# A3010_Adelaide_Keyboard.net
KiCad netlist of a schematic drawn in Altium Designer
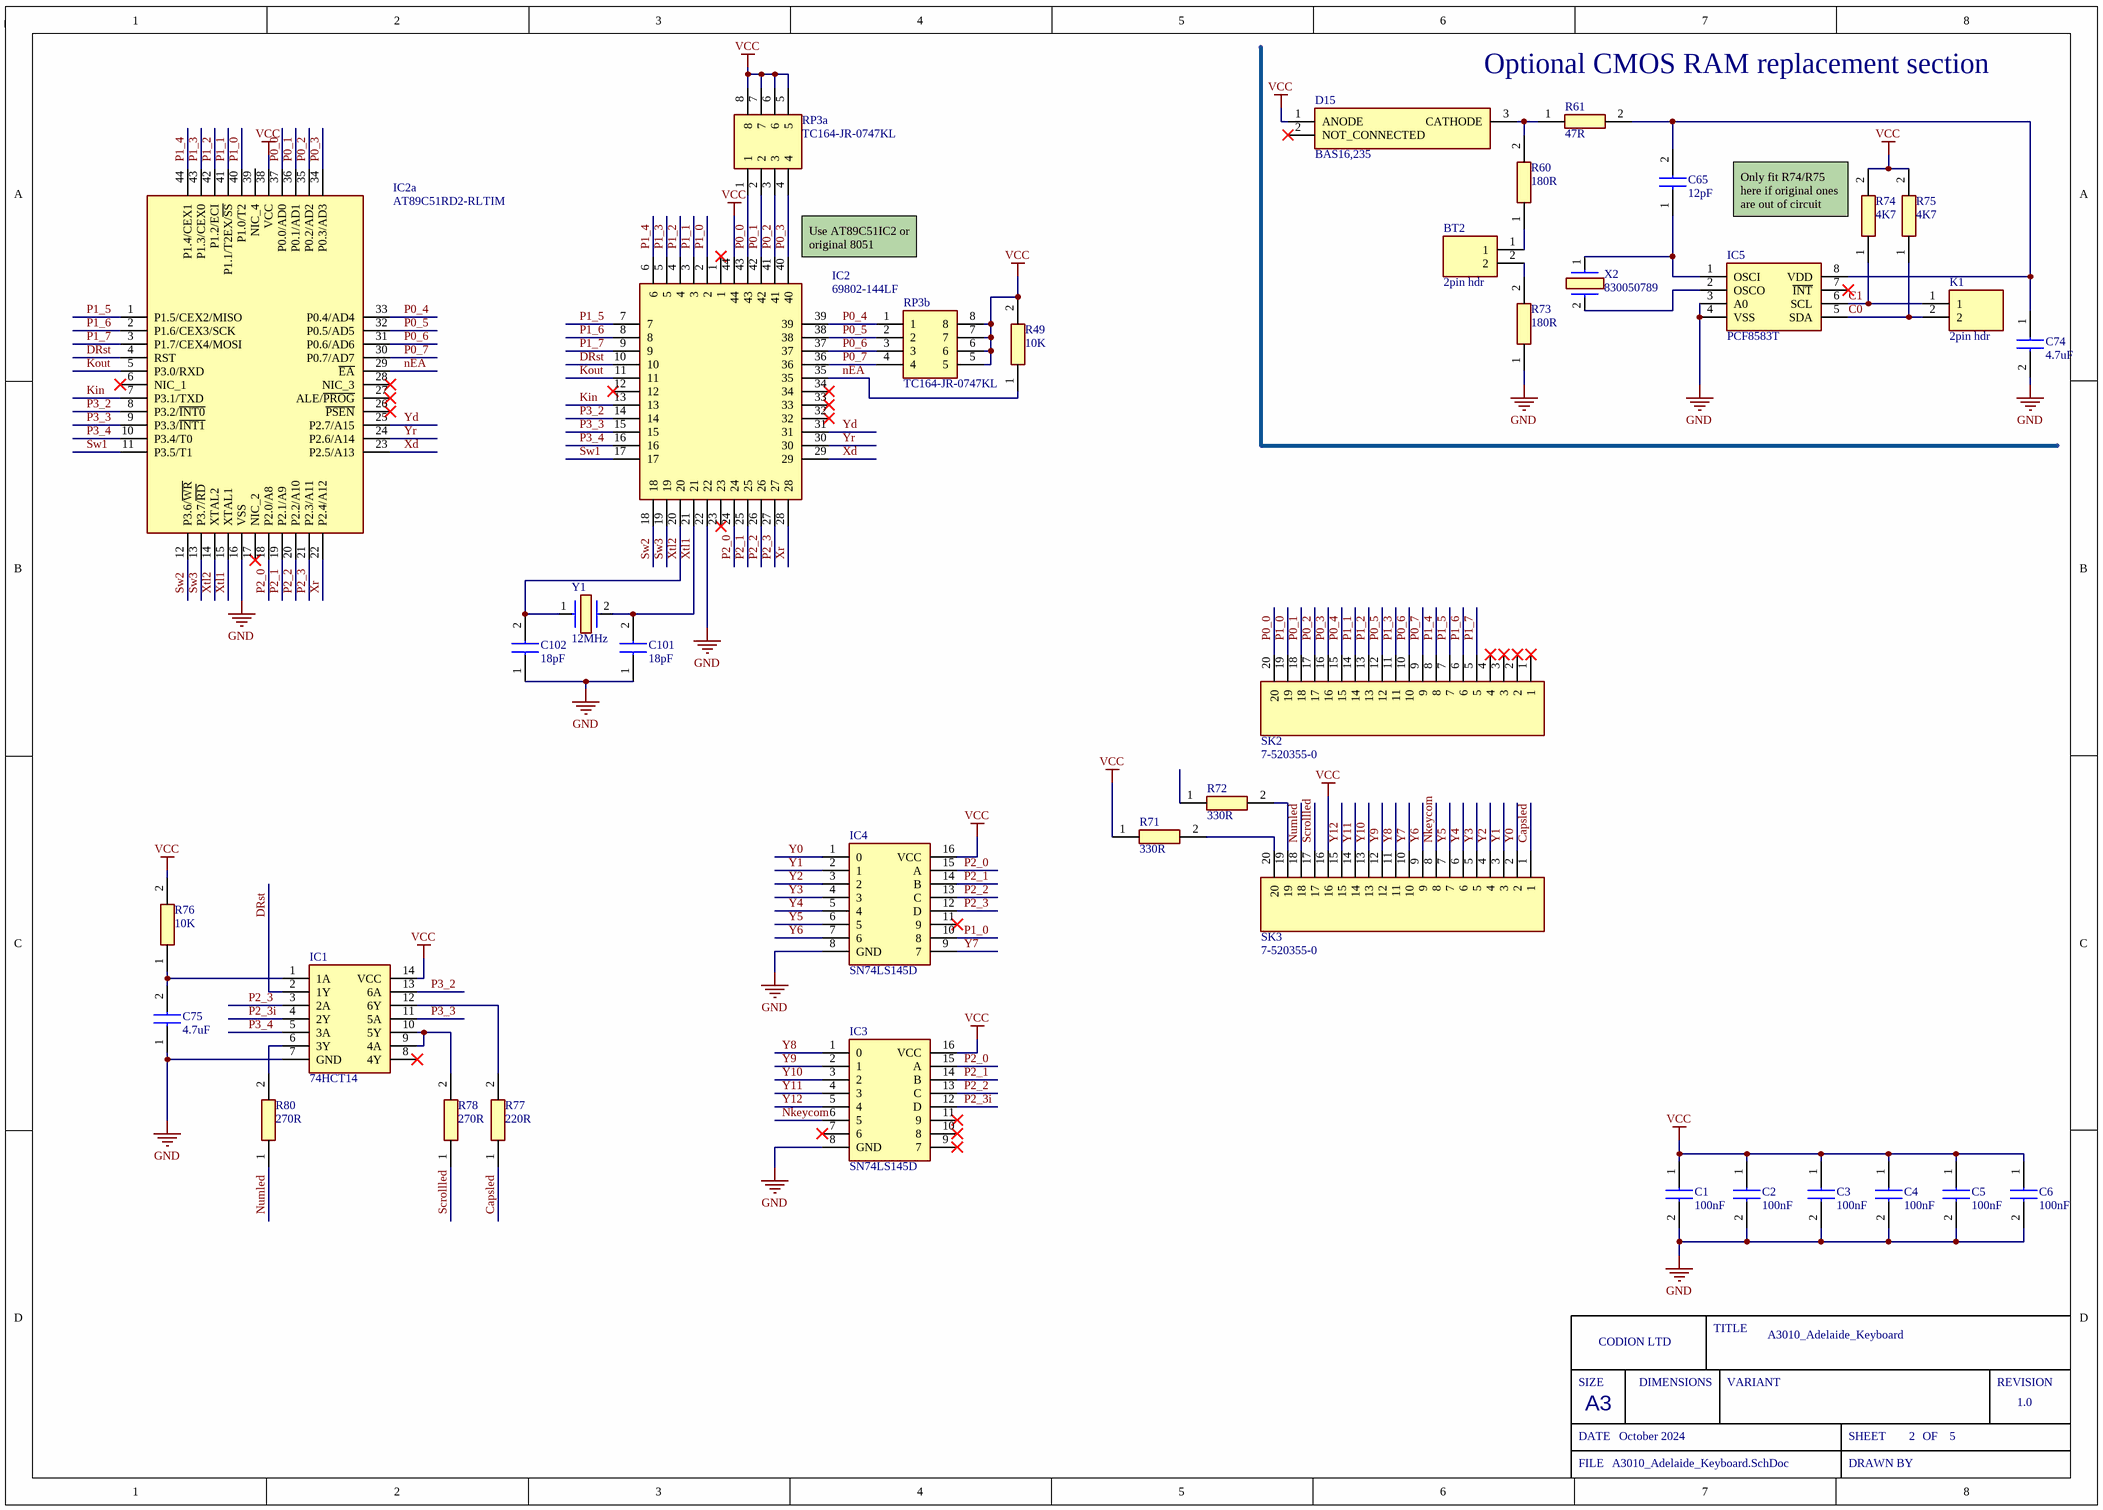
[diagram p0: A3010_Adelaide_Keyboard.SchDoc]

(export (version "E")
  (design (tool "Eeschema 10.0.6"))
  (components
    (comp (ref "BT2")
      (value "2pin hdr")
      (footprint "SamacSys:10129378902002BLF")
      (description "Connector")
      (fields (field (name "MANUFACTURER_PART_NUMBER") "10129378-902002BLF"))
      (libsource (lib "*") (part "10129378-902002BLF"))
    )
    (comp (ref "C1")
      (value "100nF")
      (footprint "0805cap")
      (description "Capacitor")
      (fields
        (field (name "MANUFACTURER_PART_NUMBER") "C2012X7R1H104K125AM")
        (field (name "MOUSER PART NUMBER") "810-C2012X7R1H104KT5")
      )
      (libsource (lib "Acorn") (part "100nF0805"))
    )
    (comp (ref "C2")
      (value "100nF")
      (footprint "0805cap")
      (description "Capacitor")
      (fields
        (field (name "MANUFACTURER_PART_NUMBER") "C2012X7R1H104K125AM")
        (field (name "MOUSER PART NUMBER") "810-C2012X7R1H104KT5")
      )
      (libsource (lib "Acorn") (part "100nF0805"))
    )
    (comp (ref "C3")
      (value "100nF")
      (footprint "0805cap")
      (description "Capacitor")
      (fields
        (field (name "MANUFACTURER_PART_NUMBER") "C2012X7R1H104K125AM")
        (field (name "MOUSER PART NUMBER") "810-C2012X7R1H104KT5")
      )
      (libsource (lib "Acorn") (part "100nF0805"))
    )
    (comp (ref "C4")
      (value "100nF")
      (footprint "0805cap")
      (description "Capacitor")
      (fields
        (field (name "MANUFACTURER_PART_NUMBER") "C2012X7R1H104K125AM")
        (field (name "MOUSER PART NUMBER") "810-C2012X7R1H104KT5")
      )
      (libsource (lib "Acorn") (part "100nF0805"))
    )
    (comp (ref "C5")
      (value "100nF")
      (footprint "0805cap")
      (description "Capacitor")
      (fields
        (field (name "MANUFACTURER_PART_NUMBER") "C2012X7R1H104K125AM")
        (field (name "MOUSER PART NUMBER") "810-C2012X7R1H104KT5")
      )
      (libsource (lib "Acorn") (part "100nF0805"))
    )
    (comp (ref "C6")
      (value "100nF")
      (footprint "0805cap")
      (description "Capacitor")
      (fields
        (field (name "MANUFACTURER_PART_NUMBER") "C2012X7R1H104K125AM")
        (field (name "MOUSER PART NUMBER") "810-C2012X7R1H104KT5")
      )
      (libsource (lib "Acorn") (part "100nF0805"))
    )
    (comp (ref "C65")
      (value "12pF")
      (footprint "SamacSys:CAPC1608X90N")
      (description "Capacitor")
      (fields (field (name "MANUFACTURER_PART_NUMBER") "CL10C120JB8NNNC"))
      (libsource (lib "*") (part "CL10C120JB8NNNC"))
    )
    (comp (ref "C74")
      (value "4.7uF")
      (footprint "0805cap")
      (description "Capacitor")
      (fields (field (name "MANUPART") "KGM21AR51C475MU"))
      (libsource (lib "Acorn") (part "4u7F0805"))
    )
    (comp (ref "C75")
      (value "4.7uF")
      (footprint "0805cap")
      (description "Capacitor")
      (fields (field (name "MANUPART") "KGM21AR51C475MU"))
      (libsource (lib "Acorn") (part "4u7F0805"))
    )
    (comp (ref "C101")
      (value "18pF")
      (footprint "SamacSys:CAPC1608X87N")
      (description "Capacitor")
      (fields
        (field (name "MANUFACTURER_PART_NUMBER") "C0603C180F5GACTU")
        (field (name "MOUSER PART NUMBER") "80-C0603C180F5G")
      )
      (libsource (lib "*") (part "C0603C180F5GACTU"))
    )
    (comp (ref "C102")
      (value "18pF")
      (footprint "SamacSys:CAPC1608X87N")
      (description "Capacitor")
      (fields
        (field (name "MANUFACTURER_PART_NUMBER") "C0603C180F5GACTU")
        (field (name "MOUSER PART NUMBER") "80-C0603C180F5G")
      )
      (libsource (lib "*") (part "C0603C180F5GACTU"))
    )
    (comp (ref "D15")
      (value "BAS16,235")
      (footprint "SamacSys:SOT95P230X110-3N")
      (description "Diode")
      (fields (field (name "MOUSER PART NUMBER") "771-BAS16235"))
      (libsource (lib "*") (part "BAS16,235"))
    )
    (comp (ref "IC1")
      (value "74HCT14")
      (footprint "SamacSys:SOIC127P600X175-14N")
      (description "Integrated Circuit")
      (fields
        (field (name "MANUFACTURER_PART_NUMBER") "74HCT14D(BJ)")
        (field (name "MOUSER PART NUMBER") "757-74HCT14DBJ")
      )
      (libsource (lib "*") (part "74HCT14D_BJ_"))
    )
    (comp (ref "IC2")
      (value "69802-144LF")
      (footprint "SamacSys:69802144LF")
      (description "Connector")
      (fields (field (name "MOUSER PART NUMBER") "649-69802-144LF"))
      (libsource (lib "*") (part "69802-144LF"))
    )
    (comp (ref "IC2a")
      (value "AT89C51RD2-RLTIM")
      (footprint "SamacSys:QFP80P1200X1200X160-44N")
      (description "Integrated Circuit")
      (libsource (lib "*") (part "AT89C51RD2-RLTIM"))
    )
    (comp (ref "IC3")
      (value "SN74LS145D")
      (footprint "SamacSys:SOIC127P600X175-16N")
      (description "Integrated Circuit")
      (fields (field (name "MOUSER PART NUMBER") "595-SN74LS145D"))
      (libsource (lib "*") (part "SN74LS145D"))
    )
    (comp (ref "IC4")
      (value "SN74LS145D")
      (footprint "SamacSys:SOIC127P600X175-16N")
      (description "Integrated Circuit")
      (fields (field (name "MOUSER PART NUMBER") "595-SN74LS145D"))
      (libsource (lib "*") (part "SN74LS145D"))
    )
    (comp (ref "IC5")
      (value "PCF8583T")
      (footprint "SamacSys:SOIC127P1032X265-8N")
      (description "Integrated Circuit")
      (fields
        (field (name "MANUFACTURER_PART_NUMBER") "PCF8583T/5,518")
        (field (name "MOUSER PART NUMBER") "771-PCF8583TD-T")
      )
      (libsource (lib "*") (part "PCF8583T_5,518"))
    )
    (comp (ref "K1")
      (value "2pin hdr")
      (footprint "SamacSys:10129378902002BLF")
      (description "Connector")
      (fields (field (name "MANUFACTURER_PART_NUMBER") "10129378-902002BLF"))
      (libsource (lib "") (part "10129378-902002BLF_1"))
    )
    (comp (ref "R49")
      (value "10K")
      (footprint "SamacSys:RESC1005X40N")
      (description "Resistor")
      (fields
        (field (name "MANUFACTURER_PART_NUMBER") "CRCW040210K0FKEDHP")
        (field (name "MOUSER PART NUMBER") "71-CRCW040210K0FKEDH")
      )
      (libsource (lib "SamacSys") (part "CRCW040210K0FKEDHP"))
    )
    (comp (ref "R60")
      (value "180R")
      (footprint "SamacSys:RESC1005X40N")
      (description "Resistor")
      (fields (field (name "MANUFACTURER_PART_NUMBER") "RC0402JR-07 180RL"))
      (libsource (lib "*") (part "RC0402JR-07_180RL"))
    )
    (comp (ref "R61")
      (value "47R")
      (footprint "SamacSys:RESC1005X40N")
      (description "Resistor")
      (fields (field (name "MANUFACTURER_PART_NUMBER") "RC0402FR-07 47RL"))
      (libsource (lib "*") (part "RC0402FR-07_47RL"))
    )
    (comp (ref "R71")
      (value "330R")
      (footprint "SamacSys:RESC1005X40N")
      (description "Resistor")
      (fields
        (field (name "MANUFACTURER_PART_NUMBER") "RC0402FR-07330RL")
        (field (name "MOUSER PART NUMBER") "603-RC0402FR-07330RL")
      )
      (libsource (lib "*") (part "RC0402FR-07330RL"))
    )
    (comp (ref "R72")
      (value "330R")
      (footprint "SamacSys:RESC1005X40N")
      (description "Resistor")
      (fields
        (field (name "MANUFACTURER_PART_NUMBER") "RC0402FR-07330RL")
        (field (name "MOUSER PART NUMBER") "603-RC0402FR-07330RL")
      )
      (libsource (lib "*") (part "RC0402FR-07330RL"))
    )
    (comp (ref "R73")
      (value "180R")
      (footprint "SamacSys:RESC1005X40N")
      (description "Resistor")
      (fields (field (name "MANUFACTURER_PART_NUMBER") "RC0402JR-07 180RL"))
      (libsource (lib "*") (part "RC0402JR-07_180RL"))
    )
    (comp (ref "R74")
      (value "4K7")
      (footprint "SamacSys:RESC1005X40N")
      (description "Resistor")
      (fields (field (name "MANUFACTURER_PART_NUMBER") "RC0402FR-07 4K7L"))
      (libsource (lib "*") (part "RC0402FR-07_4K7L"))
    )
    (comp (ref "R75")
      (value "4K7")
      (footprint "SamacSys:RESC1005X40N")
      (description "Resistor")
      (fields (field (name "MANUFACTURER_PART_NUMBER") "RC0402FR-07 4K7L"))
      (libsource (lib "*") (part "RC0402FR-07_4K7L"))
    )
    (comp (ref "R76")
      (value "10K")
      (footprint "SamacSys:RESC1005X40N")
      (description "Resistor")
      (fields
        (field (name "MANUFACTURER_PART_NUMBER") "CRCW040210K0FKEDHP")
        (field (name "MOUSER PART NUMBER") "71-CRCW040210K0FKEDH")
      )
      (libsource (lib "SamacSys") (part "CRCW040210K0FKEDHP"))
    )
    (comp (ref "R77")
      (value "220R")
      (footprint "SamacSys:RESC1005X40N")
      (description "Resistor")
      (fields
        (field (name "MANUFACTURER_PART_NUMBER") "RC0402FR-07220RL")
        (field (name "MOUSER PART NUMBER") "603-RC0402FR-07220RL")
      )
      (libsource (lib "SamacSys") (part "RC0402FR-07220RL"))
    )
    (comp (ref "R78")
      (value "270R")
      (footprint "SamacSys:RESC1005X40N")
      (description "Resistor")
      (fields
        (field (name "MANUFACTURER_PART_NUMBER") "RC0402FR-07270RL")
        (field (name "MOUSER PART NUMBER") "603-RC0402FR-07270RL")
      )
      (libsource (lib "*") (part "RC0402FR-07270RL"))
    )
    (comp (ref "R80")
      (value "270R")
      (footprint "SamacSys:RESC1005X40N")
      (description "Resistor")
      (fields
        (field (name "MANUFACTURER_PART_NUMBER") "RC0402FR-07270RL")
        (field (name "MOUSER PART NUMBER") "603-RC0402FR-07270RL")
      )
      (libsource (lib "*") (part "RC0402FR-07270RL"))
    )
    (comp (ref "RP3a")
      (value "TC164-JR-0747KL")
      (footprint "SamacSys:TC164JR0747KL")
      (description "Resistor Network")
      (libsource (lib "*") (part "TC164-JR-0747KL"))
    )
    (comp (ref "RP3b")
      (value "TC164-JR-0747KL")
      (footprint "SamacSys:TC164JR0747KL")
      (description "Resistor Network")
      (libsource (lib "") (part "TC164-JR-0747KL_1"))
    )
    (comp (ref "SK2")
      (value "7-520355-0")
      (footprint "SamacSys:75203550")
      (description "Connector")
      (fields (field (name "MOUSER PART NUMBER") "571-7-520355-0"))
      (libsource (lib "*") (part "7-520355-0"))
    )
    (comp (ref "SK3")
      (value "7-520355-0")
      (footprint "SamacSys:75203550")
      (description "Connector")
      (fields (field (name "MOUSER PART NUMBER") "571-7-520355-0"))
      (libsource (lib "*") (part "7-520355-0"))
    )
    (comp (ref "X2")
      (value "830050789")
      (footprint "SamacSys:830050789")
      (description "Crystal or Oscillator")
      (fields (field (name "MOUSER PART NUMBER") "710-830050789"))
      (libsource (lib "*") (part "830050789"))
    )
    (comp (ref "Y1")
      (value "12MHz")
      (footprint "SamacSys:ABM3")
      (description "Crystal or Oscillator")
      (fields
        (field (name "MANUFACTURER_PART_NUMBER") "ABM3-12.000MHZ-D2Y-T")
        (field (name "MOUSER PART NUMBER") "815-ABM3-12-D2Y-T")
      )
      (libsource (lib "*") (part "ABM3-12.000MHZ-D2Y-T"))
    )
  )
  (nets
    (net (code "1") (name "/C0") (class "Default")
      (node (ref "IC5") (pin "5") (pinfunction "SDA_5") (pintype "passive"))
      (node (ref "K1") (pin "2") (pinfunction "2_2") (pintype "passive"))
      (node (ref "R75") (pin "1") (pinfunction "1_1") (pintype "passive"))
    )
    (net (code "2") (name "/C1") (class "Default")
      (node (ref "IC5") (pin "6") (pinfunction "SCL_6") (pintype "passive"))
      (node (ref "K1") (pin "1") (pinfunction "1_1") (pintype "passive"))
      (node (ref "R74") (pin "1") (pinfunction "1_1") (pintype "passive"))
    )
    (net (code "3") (name "/Capsled") (class "Default")
      (node (ref "R77") (pin "1") (pinfunction "1_1") (pintype "passive"))
      (node (ref "SK3") (pin "1") (pinfunction "1_1") (pintype "passive"))
    )
    (net (code "4") (name "/DRst") (class "Default")
      (node (ref "IC1") (pin "2") (pinfunction "1Y_2") (pintype "passive"))
      (node (ref "IC2") (pin "10") (pinfunction "10_10") (pintype "passive"))
      (node (ref "IC2a") (pin "4") (pinfunction "RST_4") (pintype "passive"))
    )
    (net (code "5") (name "/Kin") (class "Default")
      (node (ref "IC2") (pin "13") (pinfunction "13_13") (pintype "passive"))
      (node (ref "IC2a") (pin "7") (pinfunction "P3.1/TXD_7") (pintype "passive"))
    )
    (net (code "6") (name "/Kout") (class "Default")
      (node (ref "IC2") (pin "11") (pinfunction "11_11") (pintype "passive"))
      (node (ref "IC2a") (pin "5") (pinfunction "P3.0/RXD_5") (pintype "passive"))
    )
    (net (code "7") (name "/Nkeycom") (class "Default")
      (node (ref "IC3") (pin "6") (pinfunction "5_6") (pintype "passive"))
      (node (ref "SK3") (pin "8") (pinfunction "8_8") (pintype "passive"))
    )
    (net (code "8") (name "/Numled") (class "Default")
      (node (ref "R80") (pin "1") (pinfunction "1_1") (pintype "passive"))
      (node (ref "SK3") (pin "18") (pinfunction "18_18") (pintype "passive"))
    )
    (net (code "9") (name "/P0_0") (class "Default")
      (node (ref "IC2") (pin "43") (pinfunction "43_43") (pintype "passive"))
      (node (ref "IC2a") (pin "37") (pinfunction "P0.0/AD0_37") (pintype "passive"))
      (node (ref "RP3a") (pin "1") (pinfunction "1_1") (pintype "passive"))
      (node (ref "SK2") (pin "20") (pinfunction "20_20") (pintype "passive"))
    )
    (net (code "10") (name "/P0_1") (class "Default")
      (node (ref "IC2") (pin "42") (pinfunction "42_42") (pintype "passive"))
      (node (ref "IC2a") (pin "36") (pinfunction "P0.1/AD1_36") (pintype "passive"))
      (node (ref "RP3a") (pin "2") (pinfunction "2_2") (pintype "passive"))
      (node (ref "SK2") (pin "18") (pinfunction "18_18") (pintype "passive"))
    )
    (net (code "11") (name "/P0_2") (class "Default")
      (node (ref "IC2") (pin "41") (pinfunction "41_41") (pintype "passive"))
      (node (ref "IC2a") (pin "35") (pinfunction "P0.2/AD2_35") (pintype "passive"))
      (node (ref "RP3a") (pin "3") (pinfunction "3_3") (pintype "passive"))
      (node (ref "SK2") (pin "17") (pinfunction "17_17") (pintype "passive"))
    )
    (net (code "12") (name "/P0_3") (class "Default")
      (node (ref "IC2") (pin "40") (pinfunction "40_40") (pintype "passive"))
      (node (ref "IC2a") (pin "34") (pinfunction "P0.3/AD3_34") (pintype "passive"))
      (node (ref "RP3a") (pin "4") (pinfunction "4_4") (pintype "passive"))
      (node (ref "SK2") (pin "16") (pinfunction "16_16") (pintype "passive"))
    )
    (net (code "13") (name "/P0_4") (class "Default")
      (node (ref "IC2") (pin "39") (pinfunction "39_39") (pintype "passive"))
      (node (ref "IC2a") (pin "33") (pinfunction "P0.4/AD4_33") (pintype "passive"))
      (node (ref "RP3b") (pin "1") (pinfunction "1_1") (pintype "passive"))
      (node (ref "SK2") (pin "15") (pinfunction "15_15") (pintype "passive"))
    )
    (net (code "14") (name "/P0_5") (class "Default")
      (node (ref "IC2") (pin "38") (pinfunction "38_38") (pintype "passive"))
      (node (ref "IC2a") (pin "32") (pinfunction "P0.5/AD5_32") (pintype "passive"))
      (node (ref "RP3b") (pin "2") (pinfunction "2_2") (pintype "passive"))
      (node (ref "SK2") (pin "12") (pinfunction "12_12") (pintype "passive"))
    )
    (net (code "15") (name "/P0_6") (class "Default")
      (node (ref "IC2") (pin "37") (pinfunction "37_37") (pintype "passive"))
      (node (ref "IC2a") (pin "31") (pinfunction "P0.6/AD6_31") (pintype "passive"))
      (node (ref "RP3b") (pin "3") (pinfunction "3_3") (pintype "passive"))
      (node (ref "SK2") (pin "10") (pinfunction "10_10") (pintype "passive"))
    )
    (net (code "16") (name "/P0_7") (class "Default")
      (node (ref "IC2") (pin "36") (pinfunction "36_36") (pintype "passive"))
      (node (ref "IC2a") (pin "30") (pinfunction "P0.7/AD7_30") (pintype "passive"))
      (node (ref "RP3b") (pin "4") (pinfunction "4_4") (pintype "passive"))
      (node (ref "SK2") (pin "9") (pinfunction "9_9") (pintype "passive"))
    )
    (net (code "17") (name "/P1_0") (class "Default")
      (node (ref "IC2") (pin "2") (pinfunction "2_2") (pintype "passive"))
      (node (ref "IC2a") (pin "40") (pinfunction "P1.0/T2_40") (pintype "passive"))
      (node (ref "IC4") (pin "10") (pinfunction "8_10") (pintype "passive"))
      (node (ref "SK2") (pin "19") (pinfunction "19_19") (pintype "passive"))
    )
    (net (code "18") (name "/P1_1") (class "Default")
      (node (ref "IC2") (pin "3") (pinfunction "3_3") (pintype "passive"))
      (node (ref "IC2a") (pin "41") (pinfunction "P1.1/T2EX/~{SS}_41") (pintype "passive"))
      (node (ref "SK2") (pin "14") (pinfunction "14_14") (pintype "passive"))
    )
    (net (code "19") (name "/P1_2") (class "Default")
      (node (ref "IC2") (pin "4") (pinfunction "4_4") (pintype "passive"))
      (node (ref "IC2a") (pin "42") (pinfunction "P1.2/ECI_42") (pintype "passive"))
      (node (ref "SK2") (pin "13") (pinfunction "13_13") (pintype "passive"))
    )
    (net (code "20") (name "/P1_3") (class "Default")
      (node (ref "IC2") (pin "5") (pinfunction "5_5") (pintype "passive"))
      (node (ref "IC2a") (pin "43") (pinfunction "P1.3/CEX0_43") (pintype "passive"))
      (node (ref "SK2") (pin "11") (pinfunction "11_11") (pintype "passive"))
    )
    (net (code "21") (name "/P1_4") (class "Default")
      (node (ref "IC2") (pin "6") (pinfunction "6_6") (pintype "passive"))
      (node (ref "IC2a") (pin "44") (pinfunction "P1.4/CEX1_44") (pintype "passive"))
      (node (ref "SK2") (pin "8") (pinfunction "8_8") (pintype "passive"))
    )
    (net (code "22") (name "/P1_5") (class "Default")
      (node (ref "IC2") (pin "7") (pinfunction "7_7") (pintype "passive"))
      (node (ref "IC2a") (pin "1") (pinfunction "P1.5/CEX2/MISO_1") (pintype "passive"))
      (node (ref "SK2") (pin "7") (pinfunction "7_7") (pintype "passive"))
    )
    (net (code "23") (name "/P1_6") (class "Default")
      (node (ref "IC2") (pin "8") (pinfunction "8_8") (pintype "passive"))
      (node (ref "IC2a") (pin "2") (pinfunction "P1.6/CEX3/SCK_2") (pintype "passive"))
      (node (ref "SK2") (pin "6") (pinfunction "6_6") (pintype "passive"))
    )
    (net (code "24") (name "/P1_7") (class "Default")
      (node (ref "IC2") (pin "9") (pinfunction "9_9") (pintype "passive"))
      (node (ref "IC2a") (pin "3") (pinfunction "P1.7/CEX4/MOSI_3") (pintype "passive"))
      (node (ref "SK2") (pin "5") (pinfunction "5_5") (pintype "passive"))
    )
    (net (code "25") (name "/P2_0") (class "Default")
      (node (ref "IC2") (pin "24") (pinfunction "24_24") (pintype "passive"))
      (node (ref "IC2a") (pin "18") (pinfunction "P2.0/A8_18") (pintype "passive"))
      (node (ref "IC3") (pin "15") (pinfunction "A_15") (pintype "passive"))
      (node (ref "IC4") (pin "15") (pinfunction "A_15") (pintype "passive"))
    )
    (net (code "26") (name "/P2_1") (class "Default")
      (node (ref "IC2") (pin "25") (pinfunction "25_25") (pintype "passive"))
      (node (ref "IC2a") (pin "19") (pinfunction "P2.1/A9_19") (pintype "passive"))
      (node (ref "IC3") (pin "14") (pinfunction "B_14") (pintype "passive"))
      (node (ref "IC4") (pin "14") (pinfunction "B_14") (pintype "passive"))
    )
    (net (code "27") (name "/P2_2") (class "Default")
      (node (ref "IC2") (pin "26") (pinfunction "26_26") (pintype "passive"))
      (node (ref "IC2a") (pin "20") (pinfunction "P2.2/A10_20") (pintype "passive"))
      (node (ref "IC3") (pin "13") (pinfunction "C_13") (pintype "passive"))
      (node (ref "IC4") (pin "13") (pinfunction "C_13") (pintype "passive"))
    )
    (net (code "28") (name "/P2_3") (class "Default")
      (node (ref "IC1") (pin "3") (pinfunction "2A_3") (pintype "passive"))
      (node (ref "IC2") (pin "27") (pinfunction "27_27") (pintype "passive"))
      (node (ref "IC2a") (pin "21") (pinfunction "P2.3/A11_21") (pintype "passive"))
      (node (ref "IC4") (pin "12") (pinfunction "D_12") (pintype "passive"))
    )
    (net (code "29") (name "/P2_3i") (class "Default")
      (node (ref "IC1") (pin "4") (pinfunction "2Y_4") (pintype "passive"))
      (node (ref "IC3") (pin "12") (pinfunction "D_12") (pintype "passive"))
    )
    (net (code "30") (name "/P3_2") (class "Default")
      (node (ref "IC1") (pin "13") (pinfunction "6A_13") (pintype "passive"))
      (node (ref "IC2") (pin "14") (pinfunction "14_14") (pintype "passive"))
      (node (ref "IC2a") (pin "8") (pinfunction "P3.2/~{INT0}_8") (pintype "passive"))
    )
    (net (code "31") (name "/P3_3") (class "Default")
      (node (ref "IC1") (pin "11") (pinfunction "5A_11") (pintype "passive"))
      (node (ref "IC2") (pin "15") (pinfunction "15_15") (pintype "passive"))
      (node (ref "IC2a") (pin "9") (pinfunction "P3.3/~{INT1}_9") (pintype "passive"))
    )
    (net (code "32") (name "/P3_4") (class "Default")
      (node (ref "IC1") (pin "5") (pinfunction "3A_5") (pintype "passive"))
      (node (ref "IC2") (pin "16") (pinfunction "16_16") (pintype "passive"))
      (node (ref "IC2a") (pin "10") (pinfunction "P3.4/T0_10") (pintype "passive"))
    )
    (net (code "33") (name "/Scrollled") (class "Default")
      (node (ref "R78") (pin "1") (pinfunction "1_1") (pintype "passive"))
      (node (ref "SK3") (pin "17") (pinfunction "17_17") (pintype "passive"))
    )
    (net (code "34") (name "/Sw1") (class "Default")
      (node (ref "IC2") (pin "17") (pinfunction "17_17") (pintype "passive"))
      (node (ref "IC2a") (pin "11") (pinfunction "P3.5/T1_11") (pintype "passive"))
    )
    (net (code "35") (name "/Sw2") (class "Default")
      (node (ref "IC2") (pin "18") (pinfunction "18_18") (pintype "passive"))
      (node (ref "IC2a") (pin "12") (pinfunction "P3.6/~{WR}_12") (pintype "passive"))
    )
    (net (code "36") (name "/Sw3") (class "Default")
      (node (ref "IC2") (pin "19") (pinfunction "19_19") (pintype "passive"))
      (node (ref "IC2a") (pin "13") (pinfunction "P3.7/~{RD}_13") (pintype "passive"))
    )
    (net (code "37") (name "/Xd") (class "Default")
      (node (ref "IC2") (pin "29") (pinfunction "29_29") (pintype "passive"))
      (node (ref "IC2a") (pin "23") (pinfunction "P2.5/A13_23") (pintype "passive"))
    )
    (net (code "38") (name "/Xr") (class "Default")
      (node (ref "IC2") (pin "28") (pinfunction "28_28") (pintype "passive"))
      (node (ref "IC2a") (pin "22") (pinfunction "P2.4/A12_22") (pintype "passive"))
    )
    (net (code "39") (name "/Xtl1") (class "Default")
      (node (ref "C101") (pin "2") (pinfunction "2_2") (pintype "passive"))
      (node (ref "IC2") (pin "21") (pinfunction "21_21") (pintype "passive"))
      (node (ref "IC2a") (pin "15") (pinfunction "XTAL1_15") (pintype "passive"))
      (node (ref "Y1") (pin "2") (pinfunction "2_2") (pintype "passive"))
    )
    (net (code "40") (name "/Xtl2") (class "Default")
      (node (ref "C102") (pin "2") (pinfunction "2_2") (pintype "passive"))
      (node (ref "IC2") (pin "20") (pinfunction "20_20") (pintype "passive"))
      (node (ref "IC2a") (pin "14") (pinfunction "XTAL2_14") (pintype "passive"))
      (node (ref "Y1") (pin "1") (pinfunction "1_1") (pintype "passive"))
    )
    (net (code "41") (name "/Y0") (class "Default")
      (node (ref "IC4") (pin "1") (pinfunction "0_1") (pintype "passive"))
      (node (ref "SK3") (pin "2") (pinfunction "2_2") (pintype "passive"))
    )
    (net (code "42") (name "/Y1") (class "Default")
      (node (ref "IC4") (pin "2") (pinfunction "1_2") (pintype "passive"))
      (node (ref "SK3") (pin "3") (pinfunction "3_3") (pintype "passive"))
    )
    (net (code "43") (name "/Y2") (class "Default")
      (node (ref "IC4") (pin "3") (pinfunction "2_3") (pintype "passive"))
      (node (ref "SK3") (pin "4") (pinfunction "4_4") (pintype "passive"))
    )
    (net (code "44") (name "/Y3") (class "Default")
      (node (ref "IC4") (pin "4") (pinfunction "3_4") (pintype "passive"))
      (node (ref "SK3") (pin "5") (pinfunction "5_5") (pintype "passive"))
    )
    (net (code "45") (name "/Y4") (class "Default")
      (node (ref "IC4") (pin "5") (pinfunction "4_5") (pintype "passive"))
      (node (ref "SK3") (pin "6") (pinfunction "6_6") (pintype "passive"))
    )
    (net (code "46") (name "/Y5") (class "Default")
      (node (ref "IC4") (pin "6") (pinfunction "5_6") (pintype "passive"))
      (node (ref "SK3") (pin "7") (pinfunction "7_7") (pintype "passive"))
    )
    (net (code "47") (name "/Y6") (class "Default")
      (node (ref "IC4") (pin "7") (pinfunction "6_7") (pintype "passive"))
      (node (ref "SK3") (pin "9") (pinfunction "9_9") (pintype "passive"))
    )
    (net (code "48") (name "/Y7") (class "Default")
      (node (ref "IC4") (pin "9") (pinfunction "7_9") (pintype "passive"))
      (node (ref "SK3") (pin "10") (pinfunction "10_10") (pintype "passive"))
    )
    (net (code "49") (name "/Y8") (class "Default")
      (node (ref "IC3") (pin "1") (pinfunction "0_1") (pintype "passive"))
      (node (ref "SK3") (pin "11") (pinfunction "11_11") (pintype "passive"))
    )
    (net (code "50") (name "/Y9") (class "Default")
      (node (ref "IC3") (pin "2") (pinfunction "1_2") (pintype "passive"))
      (node (ref "SK3") (pin "12") (pinfunction "12_12") (pintype "passive"))
    )
    (net (code "51") (name "/Y10") (class "Default")
      (node (ref "IC3") (pin "3") (pinfunction "2_3") (pintype "passive"))
      (node (ref "SK3") (pin "13") (pinfunction "13_13") (pintype "passive"))
    )
    (net (code "52") (name "/Y11") (class "Default")
      (node (ref "IC3") (pin "4") (pinfunction "3_4") (pintype "passive"))
      (node (ref "SK3") (pin "14") (pinfunction "14_14") (pintype "passive"))
    )
    (net (code "53") (name "/Y12") (class "Default")
      (node (ref "IC3") (pin "5") (pinfunction "4_5") (pintype "passive"))
      (node (ref "SK3") (pin "15") (pinfunction "15_15") (pintype "passive"))
    )
    (net (code "54") (name "/Yd") (class "Default")
      (node (ref "IC2") (pin "31") (pinfunction "31_31") (pintype "passive"))
      (node (ref "IC2a") (pin "25") (pinfunction "P2.7/A15_25") (pintype "passive"))
    )
    (net (code "55") (name "/Yr") (class "Default")
      (node (ref "IC2") (pin "30") (pinfunction "30_30") (pintype "passive"))
      (node (ref "IC2a") (pin "24") (pinfunction "P2.6/A14_24") (pintype "passive"))
    )
    (net (code "56") (name "/nEA") (class "Default")
      (node (ref "IC2") (pin "35") (pinfunction "35_35") (pintype "passive"))
      (node (ref "IC2a") (pin "29") (pinfunction "~{EA}_29") (pintype "passive"))
      (node (ref "R49") (pin "1") (pinfunction "1_1") (pintype "passive"))
    )
    (net (code "57") (name "GND") (class "Default")
      (node (ref "C1") (pin "2") (pinfunction "2_2") (pintype "passive"))
      (node (ref "C101") (pin "1") (pinfunction "1_1") (pintype "passive"))
      (node (ref "C102") (pin "1") (pinfunction "1_1") (pintype "passive"))
      (node (ref "C2") (pin "2") (pinfunction "2_2") (pintype "passive"))
      (node (ref "C3") (pin "2") (pinfunction "2_2") (pintype "passive"))
      (node (ref "C4") (pin "2") (pinfunction "2_2") (pintype "passive"))
      (node (ref "C5") (pin "2") (pinfunction "2_2") (pintype "passive"))
      (node (ref "C6") (pin "2") (pinfunction "2_2") (pintype "passive"))
      (node (ref "C74") (pin "2") (pinfunction "2_2") (pintype "passive"))
      (node (ref "C75") (pin "1") (pinfunction "1_1") (pintype "passive"))
      (node (ref "IC1") (pin "7") (pinfunction "GND_7") (pintype "passive"))
      (node (ref "IC2") (pin "22") (pinfunction "22_22") (pintype "passive"))
      (node (ref "IC2a") (pin "16") (pinfunction "VSS_16") (pintype "passive"))
      (node (ref "IC3") (pin "8") (pinfunction "GND_8") (pintype "passive"))
      (node (ref "IC4") (pin "8") (pinfunction "GND_8") (pintype "passive"))
      (node (ref "IC5") (pin "3") (pinfunction "A0_3") (pintype "passive"))
      (node (ref "IC5") (pin "4") (pinfunction "VSS_4") (pintype "passive"))
      (node (ref "R73") (pin "1") (pinfunction "1_1") (pintype "passive"))
    )
    (net (code "58") (name "Net-(BT2-Pad1)") (class "Default")
      (node (ref "BT2") (pin "1") (pinfunction "1_1") (pintype "passive"))
      (node (ref "R60") (pin "1") (pinfunction "1_1") (pintype "passive"))
    )
    (net (code "59") (name "Net-(BT2-Pad2)") (class "Default")
      (node (ref "BT2") (pin "2") (pinfunction "2_2") (pintype "passive"))
      (node (ref "R73") (pin "2") (pinfunction "2_2") (pintype "passive"))
    )
    (net (code "60") (name "Net-(D15-CATHODE)") (class "Default")
      (node (ref "D15") (pin "3") (pinfunction "CATHODE_3") (pintype "passive"))
      (node (ref "R60") (pin "2") (pinfunction "2_2") (pintype "passive"))
      (node (ref "R61") (pin "1") (pinfunction "1_1") (pintype "passive"))
    )
    (net (code "61") (name "Net-(IC1-1A)") (class "Default")
      (node (ref "C75") (pin "2") (pinfunction "2_2") (pintype "passive"))
      (node (ref "IC1") (pin "1") (pinfunction "1A_1") (pintype "passive"))
      (node (ref "R76") (pin "1") (pinfunction "1_1") (pintype "passive"))
    )
    (net (code "62") (name "Net-(IC1-3Y)") (class "Default")
      (node (ref "IC1") (pin "6") (pinfunction "3Y_6") (pintype "passive"))
      (node (ref "R80") (pin "2") (pinfunction "2_2") (pintype "passive"))
    )
    (net (code "63") (name "Net-(IC1-4A)") (class "Default")
      (node (ref "IC1") (pin "10") (pinfunction "5Y_10") (pintype "passive"))
      (node (ref "IC1") (pin "9") (pinfunction "4A_9") (pintype "passive"))
      (node (ref "R78") (pin "2") (pinfunction "2_2") (pintype "passive"))
    )
    (net (code "64") (name "Net-(IC1-6Y)") (class "Default")
      (node (ref "IC1") (pin "12") (pinfunction "6Y_12") (pintype "passive"))
      (node (ref "R77") (pin "2") (pinfunction "2_2") (pintype "passive"))
    )
    (net (code "65") (name "Net-(IC5-OSCI)") (class "Default")
      (node (ref "C65") (pin "1") (pinfunction "1_1") (pintype "passive"))
      (node (ref "IC5") (pin "1") (pinfunction "OSCI_1") (pintype "passive"))
      (node (ref "X2") (pin "1") (pinfunction "1_1") (pintype "passive"))
    )
    (net (code "66") (name "Net-(IC5-OSCO)") (class "Default")
      (node (ref "IC5") (pin "2") (pinfunction "OSCO_2") (pintype "passive"))
      (node (ref "X2") (pin "2") (pinfunction "2_2") (pintype "passive"))
    )
    (net (code "67") (name "Net-(IC5-VDD)") (class "Default")
      (node (ref "C65") (pin "2") (pinfunction "2_2") (pintype "passive"))
      (node (ref "C74") (pin "1") (pinfunction "1_1") (pintype "passive"))
      (node (ref "IC5") (pin "8") (pinfunction "VDD_8") (pintype "passive"))
      (node (ref "R61") (pin "2") (pinfunction "2_2") (pintype "passive"))
    )
    (net (code "68") (name "Net-(R71-Pad2)") (class "Default")
      (node (ref "R71") (pin "2") (pinfunction "2_2") (pintype "passive"))
      (node (ref "SK3") (pin "20") (pinfunction "20_20") (pintype "passive"))
    )
    (net (code "69") (name "Net-(R72-Pad2)") (class "Default")
      (node (ref "R72") (pin "2") (pinfunction "2_2") (pintype "passive"))
      (node (ref "SK3") (pin "19") (pinfunction "19_19") (pintype "passive"))
    )
    (net (code "70") (name "VCC") (class "Default")
      (node (ref "C1") (pin "1") (pinfunction "1_1") (pintype "passive"))
      (node (ref "C2") (pin "1") (pinfunction "1_1") (pintype "passive"))
      (node (ref "C3") (pin "1") (pinfunction "1_1") (pintype "passive"))
      (node (ref "C4") (pin "1") (pinfunction "1_1") (pintype "passive"))
      (node (ref "C5") (pin "1") (pinfunction "1_1") (pintype "passive"))
      (node (ref "C6") (pin "1") (pinfunction "1_1") (pintype "passive"))
      (node (ref "D15") (pin "1") (pinfunction "ANODE_1") (pintype "passive"))
      (node (ref "IC1") (pin "14") (pinfunction "VCC_14") (pintype "passive"))
      (node (ref "IC2") (pin "44") (pinfunction "44_44") (pintype "passive"))
      (node (ref "IC2a") (pin "38") (pinfunction "VCC_38") (pintype "passive"))
      (node (ref "IC3") (pin "16") (pinfunction "VCC_16") (pintype "passive"))
      (node (ref "IC4") (pin "16") (pinfunction "VCC_16") (pintype "passive"))
      (node (ref "R49") (pin "2") (pinfunction "2_2") (pintype "passive"))
      (node (ref "R71") (pin "1") (pinfunction "1_1") (pintype "passive"))
      (node (ref "R74") (pin "2") (pinfunction "2_2") (pintype "passive"))
      (node (ref "R75") (pin "2") (pinfunction "2_2") (pintype "passive"))
      (node (ref "R76") (pin "2") (pinfunction "2_2") (pintype "passive"))
      (node (ref "RP3a") (pin "5") (pinfunction "5_5") (pintype "passive"))
      (node (ref "RP3a") (pin "6") (pinfunction "6_6") (pintype "passive"))
      (node (ref "RP3a") (pin "7") (pinfunction "7_7") (pintype "passive"))
      (node (ref "RP3a") (pin "8") (pinfunction "8_8") (pintype "passive"))
      (node (ref "RP3b") (pin "5") (pinfunction "5_5") (pintype "passive"))
      (node (ref "RP3b") (pin "6") (pinfunction "6_6") (pintype "passive"))
      (node (ref "RP3b") (pin "7") (pinfunction "7_7") (pintype "passive"))
      (node (ref "RP3b") (pin "8") (pinfunction "8_8") (pintype "passive"))
      (node (ref "SK3") (pin "16") (pinfunction "16_16") (pintype "passive"))
    )
    (net (code "71") (name "unconnected-(D15-NOT_CONNECTED-Pad2)") (class "Default")
      (node (ref "D15") (pin "2") (pinfunction "NOT_CONNECTED_2") (pintype "passive+no_connect"))
    )
    (net (code "72") (name "unconnected-(IC1-4Y-Pad8)") (class "Default")
      (node (ref "IC1") (pin "8") (pinfunction "4Y_8") (pintype "passive+no_connect"))
    )
    (net (code "73") (name "unconnected-(IC2-Pad1)") (class "Default")
      (node (ref "IC2") (pin "1") (pinfunction "1_1") (pintype "passive+no_connect"))
    )
    (net (code "74") (name "unconnected-(IC2-Pad12)") (class "Default")
      (node (ref "IC2") (pin "12") (pinfunction "12_12") (pintype "passive+no_connect"))
    )
    (net (code "75") (name "unconnected-(IC2-Pad23)") (class "Default")
      (node (ref "IC2") (pin "23") (pinfunction "23_23") (pintype "passive+no_connect"))
    )
    (net (code "76") (name "unconnected-(IC2-Pad32)") (class "Default")
      (node (ref "IC2") (pin "32") (pinfunction "32_32") (pintype "passive+no_connect"))
    )
    (net (code "77") (name "unconnected-(IC2-Pad33)") (class "Default")
      (node (ref "IC2") (pin "33") (pinfunction "33_33") (pintype "passive+no_connect"))
    )
    (net (code "78") (name "unconnected-(IC2-Pad34)") (class "Default")
      (node (ref "IC2") (pin "34") (pinfunction "34_34") (pintype "passive+no_connect"))
    )
    (net (code "79") (name "unconnected-(IC2a-ALE{slash}~{PROG}-Pad27)") (class "Default")
      (node (ref "IC2a") (pin "27") (pinfunction "ALE/~{PROG}_27") (pintype "passive+no_connect"))
    )
    (net (code "80") (name "unconnected-(IC2a-NIC_1-Pad6)") (class "Default")
      (node (ref "IC2a") (pin "6") (pinfunction "NIC_1_6") (pintype "passive+no_connect"))
    )
    (net (code "81") (name "unconnected-(IC2a-NIC_2-Pad17)") (class "Default")
      (node (ref "IC2a") (pin "17") (pinfunction "NIC_2_17") (pintype "passive+no_connect"))
    )
    (net (code "82") (name "unconnected-(IC2a-NIC_3-Pad28)") (class "Default")
      (node (ref "IC2a") (pin "28") (pinfunction "NIC_3_28") (pintype "passive+no_connect"))
    )
    (net (code "83") (name "unconnected-(IC2a-NIC_4-Pad39)") (class "Default")
      (node (ref "IC2a") (pin "39") (pinfunction "NIC_4_39") (pintype "passive"))
    )
    (net (code "84") (name "unconnected-(IC2a-~{PSEN}-Pad26)") (class "Default")
      (node (ref "IC2a") (pin "26") (pinfunction "~{PSEN}_26") (pintype "passive+no_connect"))
    )
    (net (code "85") (name "unconnected-(IC3-6-Pad7)") (class "Default")
      (node (ref "IC3") (pin "7") (pinfunction "6_7") (pintype "passive+no_connect"))
    )
    (net (code "86") (name "unconnected-(IC3-7-Pad9)") (class "Default")
      (node (ref "IC3") (pin "9") (pinfunction "7_9") (pintype "passive+no_connect"))
    )
    (net (code "87") (name "unconnected-(IC3-8-Pad10)") (class "Default")
      (node (ref "IC3") (pin "10") (pinfunction "8_10") (pintype "passive+no_connect"))
    )
    (net (code "88") (name "unconnected-(IC3-9-Pad11)") (class "Default")
      (node (ref "IC3") (pin "11") (pinfunction "9_11") (pintype "passive+no_connect"))
    )
    (net (code "89") (name "unconnected-(IC4-9-Pad11)") (class "Default")
      (node (ref "IC4") (pin "11") (pinfunction "9_11") (pintype "passive+no_connect"))
    )
    (net (code "90") (name "unconnected-(IC5-~{INT}-Pad7)") (class "Default")
      (node (ref "IC5") (pin "7") (pinfunction "~{INT}_7") (pintype "passive+no_connect"))
    )
    (net (code "91") (name "unconnected-(R72-Pad1)") (class "Default")
      (node (ref "R72") (pin "1") (pinfunction "1_1") (pintype "passive"))
    )
    (net (code "92") (name "unconnected-(SK2-Pad1)") (class "Default")
      (node (ref "SK2") (pin "1") (pinfunction "1_1") (pintype "passive+no_connect"))
    )
    (net (code "93") (name "unconnected-(SK2-Pad2)") (class "Default")
      (node (ref "SK2") (pin "2") (pinfunction "2_2") (pintype "passive+no_connect"))
    )
    (net (code "94") (name "unconnected-(SK2-Pad3)") (class "Default")
      (node (ref "SK2") (pin "3") (pinfunction "3_3") (pintype "passive+no_connect"))
    )
    (net (code "95") (name "unconnected-(SK2-Pad4)") (class "Default")
      (node (ref "SK2") (pin "4") (pinfunction "4_4") (pintype "passive+no_connect"))
    )
  )
)
